# Sheet2.net
KiCad netlist of a schematic drawn in Altium Designer
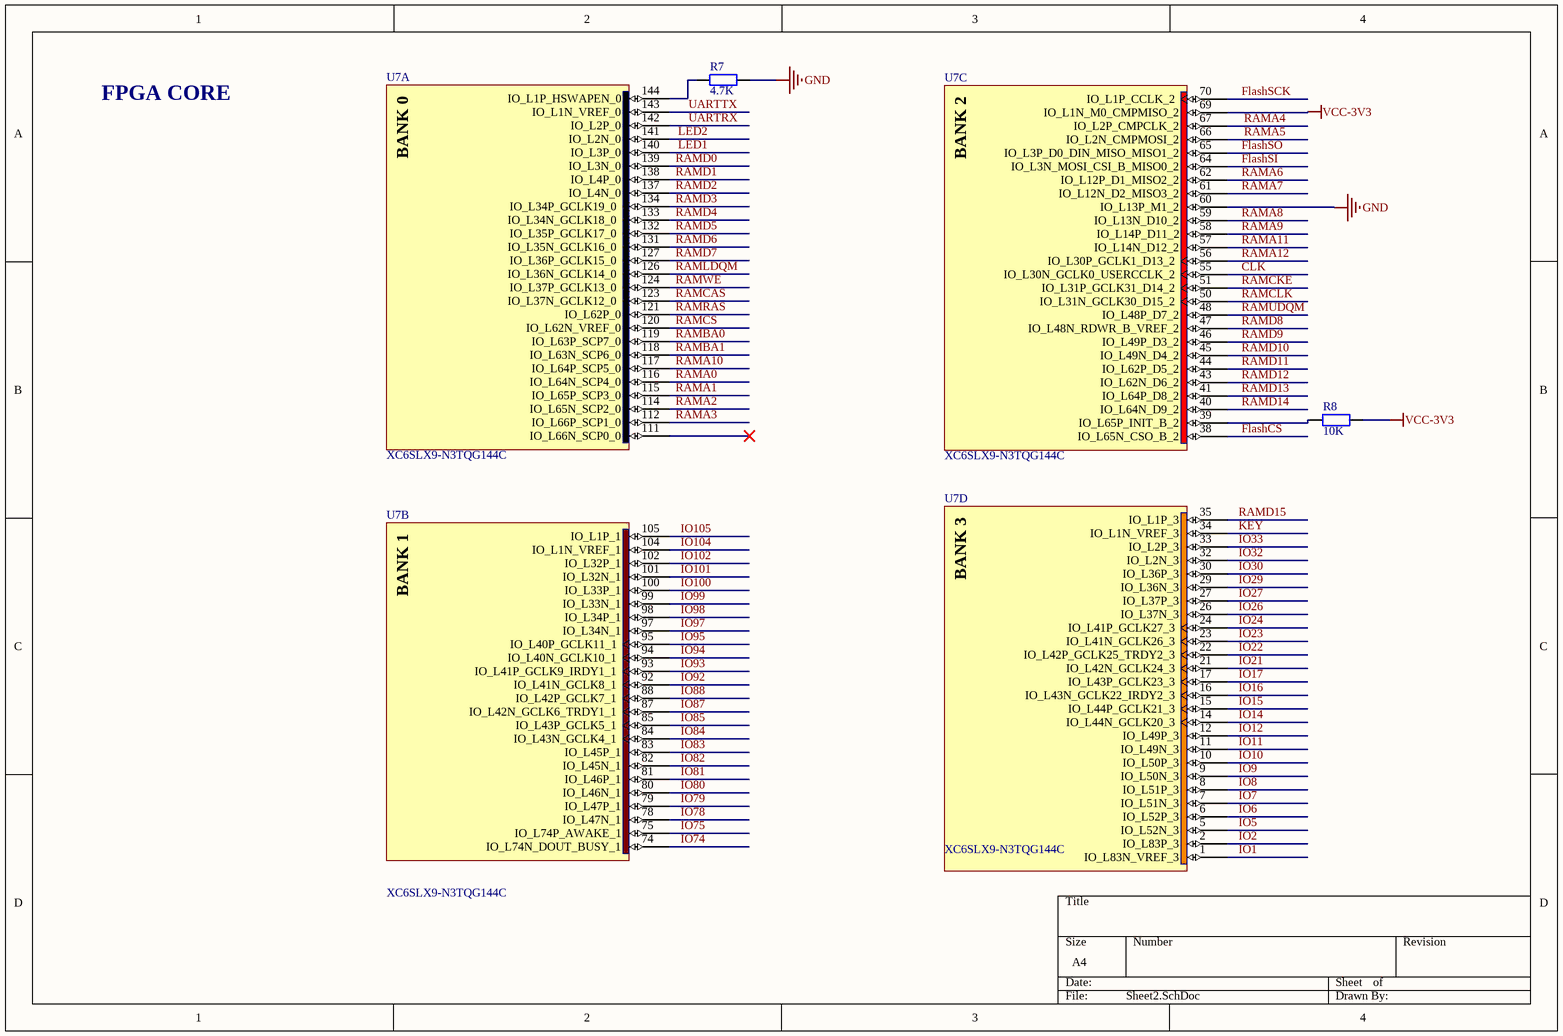
[diagram p0: Sheet2.SchDoc]

(export (version "E")
  (design (tool "Eeschema 10.0.6"))
  (components
    (comp (ref "R7")
      (value "4.7K")
      (footprint "0603_R")
      (description "贴片电阻")
      (libsource (lib "RES") (part "0603 9.1KΩ (9101) 1%"))
    )
    (comp (ref "R8")
      (value "10K")
      (footprint "0603_R")
      (description "贴片电阻")
      (libsource (lib "") (part "0603 9.1KΩ (9101) 1%_1"))
    )
    (comp (ref "U7")
      (value "XC6SLX9-N3TQG144C")
      (footprint "TQG144_N")
      (fields (field (name "PUBLISHER") "Altium Limited"))
      (libsource (lib "Xilinx Spartan-6") (part "XC6SLX9-N3TQG144C"))
    )
  )
  (nets
    (net (code "1") (name "/CLK") (class "Default")
      (node (ref "U7") (pin "55") (pinfunction "IO_L30N_GCLK0_USERCCLK_2_55") (pintype "bidirectional"))
    )
    (net (code "2") (name "/FlashCS") (class "Default")
      (node (ref "U7") (pin "38") (pinfunction "IO_L65N_CSO_B_2_38") (pintype "bidirectional"))
    )
    (net (code "3") (name "/FlashSCK") (class "Default")
      (node (ref "U7") (pin "70") (pinfunction "IO_L1P_CCLK_2_70") (pintype "bidirectional"))
    )
    (net (code "4") (name "/FlashSI") (class "Default")
      (node (ref "U7") (pin "64") (pinfunction "IO_L3N_MOSI_CSI_B_MISO0_2_64") (pintype "bidirectional"))
    )
    (net (code "5") (name "/FlashSO") (class "Default")
      (node (ref "U7") (pin "65") (pinfunction "IO_L3P_D0_DIN_MISO_MISO1_2_65") (pintype "bidirectional"))
    )
    (net (code "6") (name "/IO1") (class "Default")
      (node (ref "U7") (pin "1") (pinfunction "IO_L83N_VREF_3_1") (pintype "bidirectional"))
    )
    (net (code "7") (name "/IO2") (class "Default")
      (node (ref "U7") (pin "2") (pinfunction "IO_L83P_3_2") (pintype "bidirectional"))
    )
    (net (code "8") (name "/IO5") (class "Default")
      (node (ref "U7") (pin "5") (pinfunction "IO_L52N_3_5") (pintype "bidirectional"))
    )
    (net (code "9") (name "/IO6") (class "Default")
      (node (ref "U7") (pin "6") (pinfunction "IO_L52P_3_6") (pintype "bidirectional"))
    )
    (net (code "10") (name "/IO7") (class "Default")
      (node (ref "U7") (pin "7") (pinfunction "IO_L51N_3_7") (pintype "bidirectional"))
    )
    (net (code "11") (name "/IO8") (class "Default")
      (node (ref "U7") (pin "8") (pinfunction "IO_L51P_3_8") (pintype "bidirectional"))
    )
    (net (code "12") (name "/IO9") (class "Default")
      (node (ref "U7") (pin "9") (pinfunction "IO_L50N_3_9") (pintype "bidirectional"))
    )
    (net (code "13") (name "/IO10") (class "Default")
      (node (ref "U7") (pin "10") (pinfunction "IO_L50P_3_10") (pintype "bidirectional"))
    )
    (net (code "14") (name "/IO11") (class "Default")
      (node (ref "U7") (pin "11") (pinfunction "IO_L49N_3_11") (pintype "bidirectional"))
    )
    (net (code "15") (name "/IO12") (class "Default")
      (node (ref "U7") (pin "12") (pinfunction "IO_L49P_3_12") (pintype "bidirectional"))
    )
    (net (code "16") (name "/IO14") (class "Default")
      (node (ref "U7") (pin "14") (pinfunction "IO_L44N_GCLK20_3_14") (pintype "bidirectional"))
    )
    (net (code "17") (name "/IO15") (class "Default")
      (node (ref "U7") (pin "15") (pinfunction "IO_L44P_GCLK21_3_15") (pintype "bidirectional"))
    )
    (net (code "18") (name "/IO16") (class "Default")
      (node (ref "U7") (pin "16") (pinfunction "IO_L43N_GCLK22_IRDY2_3_16") (pintype "bidirectional"))
    )
    (net (code "19") (name "/IO17") (class "Default")
      (node (ref "U7") (pin "17") (pinfunction "IO_L43P_GCLK23_3_17") (pintype "bidirectional"))
    )
    (net (code "20") (name "/IO21") (class "Default")
      (node (ref "U7") (pin "21") (pinfunction "IO_L42N_GCLK24_3_21") (pintype "bidirectional"))
    )
    (net (code "21") (name "/IO22") (class "Default")
      (node (ref "U7") (pin "22") (pinfunction "IO_L42P_GCLK25_TRDY2_3_22") (pintype "bidirectional"))
    )
    (net (code "22") (name "/IO23") (class "Default")
      (node (ref "U7") (pin "23") (pinfunction "IO_L41N_GCLK26_3_23") (pintype "bidirectional"))
    )
    (net (code "23") (name "/IO24") (class "Default")
      (node (ref "U7") (pin "24") (pinfunction "IO_L41P_GCLK27_3_24") (pintype "bidirectional"))
    )
    (net (code "24") (name "/IO26") (class "Default")
      (node (ref "U7") (pin "26") (pinfunction "IO_L37N_3_26") (pintype "bidirectional"))
    )
    (net (code "25") (name "/IO27") (class "Default")
      (node (ref "U7") (pin "27") (pinfunction "IO_L37P_3_27") (pintype "bidirectional"))
    )
    (net (code "26") (name "/IO29") (class "Default")
      (node (ref "U7") (pin "29") (pinfunction "IO_L36N_3_29") (pintype "bidirectional"))
    )
    (net (code "27") (name "/IO30") (class "Default")
      (node (ref "U7") (pin "30") (pinfunction "IO_L36P_3_30") (pintype "bidirectional"))
    )
    (net (code "28") (name "/IO32") (class "Default")
      (node (ref "U7") (pin "32") (pinfunction "IO_L2N_3_32") (pintype "bidirectional"))
    )
    (net (code "29") (name "/IO33") (class "Default")
      (node (ref "U7") (pin "33") (pinfunction "IO_L2P_3_33") (pintype "bidirectional"))
    )
    (net (code "30") (name "/IO74") (class "Default")
      (node (ref "U7") (pin "74") (pinfunction "IO_L74N_DOUT_BUSY_1_74") (pintype "bidirectional"))
    )
    (net (code "31") (name "/IO75") (class "Default")
      (node (ref "U7") (pin "75") (pinfunction "IO_L74P_AWAKE_1_75") (pintype "bidirectional"))
    )
    (net (code "32") (name "/IO78") (class "Default")
      (node (ref "U7") (pin "78") (pinfunction "IO_L47N_1_78") (pintype "bidirectional"))
    )
    (net (code "33") (name "/IO79") (class "Default")
      (node (ref "U7") (pin "79") (pinfunction "IO_L47P_1_79") (pintype "bidirectional"))
    )
    (net (code "34") (name "/IO80") (class "Default")
      (node (ref "U7") (pin "80") (pinfunction "IO_L46N_1_80") (pintype "bidirectional"))
    )
    (net (code "35") (name "/IO81") (class "Default")
      (node (ref "U7") (pin "81") (pinfunction "IO_L46P_1_81") (pintype "bidirectional"))
    )
    (net (code "36") (name "/IO82") (class "Default")
      (node (ref "U7") (pin "82") (pinfunction "IO_L45N_1_82") (pintype "bidirectional"))
    )
    (net (code "37") (name "/IO83") (class "Default")
      (node (ref "U7") (pin "83") (pinfunction "IO_L45P_1_83") (pintype "bidirectional"))
    )
    (net (code "38") (name "/IO84") (class "Default")
      (node (ref "U7") (pin "84") (pinfunction "IO_L43N_GCLK4_1_84") (pintype "bidirectional"))
    )
    (net (code "39") (name "/IO85") (class "Default")
      (node (ref "U7") (pin "85") (pinfunction "IO_L43P_GCLK5_1_85") (pintype "bidirectional"))
    )
    (net (code "40") (name "/IO87") (class "Default")
      (node (ref "U7") (pin "87") (pinfunction "IO_L42N_GCLK6_TRDY1_1_87") (pintype "bidirectional"))
    )
    (net (code "41") (name "/IO88") (class "Default")
      (node (ref "U7") (pin "88") (pinfunction "IO_L42P_GCLK7_1_88") (pintype "bidirectional"))
    )
    (net (code "42") (name "/IO92") (class "Default")
      (node (ref "U7") (pin "92") (pinfunction "IO_L41N_GCLK8_1_92") (pintype "bidirectional"))
    )
    (net (code "43") (name "/IO93") (class "Default")
      (node (ref "U7") (pin "93") (pinfunction "IO_L41P_GCLK9_IRDY1_1_93") (pintype "bidirectional"))
    )
    (net (code "44") (name "/IO94") (class "Default")
      (node (ref "U7") (pin "94") (pinfunction "IO_L40N_GCLK10_1_94") (pintype "bidirectional"))
    )
    (net (code "45") (name "/IO95") (class "Default")
      (node (ref "U7") (pin "95") (pinfunction "IO_L40P_GCLK11_1_95") (pintype "bidirectional"))
    )
    (net (code "46") (name "/IO97") (class "Default")
      (node (ref "U7") (pin "97") (pinfunction "IO_L34N_1_97") (pintype "bidirectional"))
    )
    (net (code "47") (name "/IO98") (class "Default")
      (node (ref "U7") (pin "98") (pinfunction "IO_L34P_1_98") (pintype "bidirectional"))
    )
    (net (code "48") (name "/IO99") (class "Default")
      (node (ref "U7") (pin "99") (pinfunction "IO_L33N_1_99") (pintype "bidirectional"))
    )
    (net (code "49") (name "/IO100") (class "Default")
      (node (ref "U7") (pin "100") (pinfunction "IO_L33P_1_100") (pintype "bidirectional"))
    )
    (net (code "50") (name "/IO101") (class "Default")
      (node (ref "U7") (pin "101") (pinfunction "IO_L32N_1_101") (pintype "bidirectional"))
    )
    (net (code "51") (name "/IO102") (class "Default")
      (node (ref "U7") (pin "102") (pinfunction "IO_L32P_1_102") (pintype "bidirectional"))
    )
    (net (code "52") (name "/IO104") (class "Default")
      (node (ref "U7") (pin "104") (pinfunction "IO_L1N_VREF_1_104") (pintype "bidirectional"))
    )
    (net (code "53") (name "/IO105") (class "Default")
      (node (ref "U7") (pin "105") (pinfunction "IO_L1P_1_105") (pintype "bidirectional"))
    )
    (net (code "54") (name "/KEY") (class "Default")
      (node (ref "U7") (pin "34") (pinfunction "IO_L1N_VREF_3_34") (pintype "bidirectional"))
    )
    (net (code "55") (name "/LED1") (class "Default")
      (node (ref "U7") (pin "140") (pinfunction "IO_L3P_0_140") (pintype "bidirectional"))
    )
    (net (code "56") (name "/LED2") (class "Default")
      (node (ref "U7") (pin "141") (pinfunction "IO_L2N_0_141") (pintype "bidirectional"))
    )
    (net (code "57") (name "/RAMA0") (class "Default")
      (node (ref "U7") (pin "116") (pinfunction "IO_L64N_SCP4_0_116") (pintype "bidirectional"))
    )
    (net (code "58") (name "/RAMA1") (class "Default")
      (node (ref "U7") (pin "115") (pinfunction "IO_L65P_SCP3_0_115") (pintype "bidirectional"))
    )
    (net (code "59") (name "/RAMA2") (class "Default")
      (node (ref "U7") (pin "114") (pinfunction "IO_L65N_SCP2_0_114") (pintype "bidirectional"))
    )
    (net (code "60") (name "/RAMA3") (class "Default")
      (node (ref "U7") (pin "112") (pinfunction "IO_L66P_SCP1_0_112") (pintype "bidirectional"))
    )
    (net (code "61") (name "/RAMA4") (class "Default")
      (node (ref "U7") (pin "67") (pinfunction "IO_L2P_CMPCLK_2_67") (pintype "bidirectional"))
    )
    (net (code "62") (name "/RAMA5") (class "Default")
      (node (ref "U7") (pin "66") (pinfunction "IO_L2N_CMPMOSI_2_66") (pintype "bidirectional"))
    )
    (net (code "63") (name "/RAMA6") (class "Default")
      (node (ref "U7") (pin "62") (pinfunction "IO_L12P_D1_MISO2_2_62") (pintype "bidirectional"))
    )
    (net (code "64") (name "/RAMA7") (class "Default")
      (node (ref "U7") (pin "61") (pinfunction "IO_L12N_D2_MISO3_2_61") (pintype "bidirectional"))
    )
    (net (code "65") (name "/RAMA8") (class "Default")
      (node (ref "U7") (pin "59") (pinfunction "IO_L13N_D10_2_59") (pintype "bidirectional"))
    )
    (net (code "66") (name "/RAMA9") (class "Default")
      (node (ref "U7") (pin "58") (pinfunction "IO_L14P_D11_2_58") (pintype "bidirectional"))
    )
    (net (code "67") (name "/RAMA10") (class "Default")
      (node (ref "U7") (pin "117") (pinfunction "IO_L64P_SCP5_0_117") (pintype "bidirectional"))
    )
    (net (code "68") (name "/RAMA11") (class "Default")
      (node (ref "U7") (pin "57") (pinfunction "IO_L14N_D12_2_57") (pintype "bidirectional"))
    )
    (net (code "69") (name "/RAMA12") (class "Default")
      (node (ref "U7") (pin "56") (pinfunction "IO_L30P_GCLK1_D13_2_56") (pintype "bidirectional"))
    )
    (net (code "70") (name "/RAMBA0") (class "Default")
      (node (ref "U7") (pin "119") (pinfunction "IO_L63P_SCP7_0_119") (pintype "bidirectional"))
    )
    (net (code "71") (name "/RAMBA1") (class "Default")
      (node (ref "U7") (pin "118") (pinfunction "IO_L63N_SCP6_0_118") (pintype "bidirectional"))
    )
    (net (code "72") (name "/RAMCAS") (class "Default")
      (node (ref "U7") (pin "123") (pinfunction "IO_L37N_GCLK12_0_123") (pintype "bidirectional"))
    )
    (net (code "73") (name "/RAMCKE") (class "Default")
      (node (ref "U7") (pin "51") (pinfunction "IO_L31P_GCLK31_D14_2_51") (pintype "bidirectional"))
    )
    (net (code "74") (name "/RAMCLK") (class "Default")
      (node (ref "U7") (pin "50") (pinfunction "IO_L31N_GCLK30_D15_2_50") (pintype "bidirectional"))
    )
    (net (code "75") (name "/RAMCS") (class "Default")
      (node (ref "U7") (pin "120") (pinfunction "IO_L62N_VREF_0_120") (pintype "bidirectional"))
    )
    (net (code "76") (name "/RAMD0") (class "Default")
      (node (ref "U7") (pin "139") (pinfunction "IO_L3N_0_139") (pintype "bidirectional"))
    )
    (net (code "77") (name "/RAMD1") (class "Default")
      (node (ref "U7") (pin "138") (pinfunction "IO_L4P_0_138") (pintype "bidirectional"))
    )
    (net (code "78") (name "/RAMD2") (class "Default")
      (node (ref "U7") (pin "137") (pinfunction "IO_L4N_0_137") (pintype "bidirectional"))
    )
    (net (code "79") (name "/RAMD3") (class "Default")
      (node (ref "U7") (pin "134") (pinfunction "IO_L34P_GCLK19_0_134") (pintype "bidirectional"))
    )
    (net (code "80") (name "/RAMD4") (class "Default")
      (node (ref "U7") (pin "133") (pinfunction "IO_L34N_GCLK18_0_133") (pintype "bidirectional"))
    )
    (net (code "81") (name "/RAMD5") (class "Default")
      (node (ref "U7") (pin "132") (pinfunction "IO_L35P_GCLK17_0_132") (pintype "bidirectional"))
    )
    (net (code "82") (name "/RAMD6") (class "Default")
      (node (ref "U7") (pin "131") (pinfunction "IO_L35N_GCLK16_0_131") (pintype "bidirectional"))
    )
    (net (code "83") (name "/RAMD7") (class "Default")
      (node (ref "U7") (pin "127") (pinfunction "IO_L36P_GCLK15_0_127") (pintype "bidirectional"))
    )
    (net (code "84") (name "/RAMD8") (class "Default")
      (node (ref "U7") (pin "47") (pinfunction "IO_L48N_RDWR_B_VREF_2_47") (pintype "bidirectional"))
    )
    (net (code "85") (name "/RAMD9") (class "Default")
      (node (ref "U7") (pin "46") (pinfunction "IO_L49P_D3_2_46") (pintype "bidirectional"))
    )
    (net (code "86") (name "/RAMD10") (class "Default")
      (node (ref "U7") (pin "45") (pinfunction "IO_L49N_D4_2_45") (pintype "bidirectional"))
    )
    (net (code "87") (name "/RAMD11") (class "Default")
      (node (ref "U7") (pin "44") (pinfunction "IO_L62P_D5_2_44") (pintype "bidirectional"))
    )
    (net (code "88") (name "/RAMD12") (class "Default")
      (node (ref "U7") (pin "43") (pinfunction "IO_L62N_D6_2_43") (pintype "bidirectional"))
    )
    (net (code "89") (name "/RAMD13") (class "Default")
      (node (ref "U7") (pin "41") (pinfunction "IO_L64P_D8_2_41") (pintype "bidirectional"))
    )
    (net (code "90") (name "/RAMD14") (class "Default")
      (node (ref "U7") (pin "40") (pinfunction "IO_L64N_D9_2_40") (pintype "bidirectional"))
    )
    (net (code "91") (name "/RAMD15") (class "Default")
      (node (ref "U7") (pin "35") (pinfunction "IO_L1P_3_35") (pintype "bidirectional"))
    )
    (net (code "92") (name "/RAMLDQM") (class "Default")
      (node (ref "U7") (pin "126") (pinfunction "IO_L36N_GCLK14_0_126") (pintype "bidirectional"))
    )
    (net (code "93") (name "/RAMRAS") (class "Default")
      (node (ref "U7") (pin "121") (pinfunction "IO_L62P_0_121") (pintype "bidirectional"))
    )
    (net (code "94") (name "/RAMUDQM") (class "Default")
      (node (ref "U7") (pin "48") (pinfunction "IO_L48P_D7_2_48") (pintype "bidirectional"))
    )
    (net (code "95") (name "/RAMWE") (class "Default")
      (node (ref "U7") (pin "124") (pinfunction "IO_L37P_GCLK13_0_124") (pintype "bidirectional"))
    )
    (net (code "96") (name "/UARTRX") (class "Default")
      (node (ref "U7") (pin "142") (pinfunction "IO_L2P_0_142") (pintype "bidirectional"))
    )
    (net (code "97") (name "/UARTTX") (class "Default")
      (node (ref "U7") (pin "143") (pinfunction "IO_L1N_VREF_0_143") (pintype "bidirectional"))
    )
    (net (code "98") (name "GND") (class "Default")
      (node (ref "R7") (pin "2") (pinfunction "2_2") (pintype "passive"))
      (node (ref "U7") (pin "60") (pinfunction "IO_L13P_M1_2_60") (pintype "bidirectional"))
    )
    (net (code "99") (name "Net-(U7A-IO_L1P_HSWAPEN_0)") (class "Default")
      (node (ref "R7") (pin "1") (pinfunction "1_1") (pintype "passive"))
      (node (ref "U7") (pin "144") (pinfunction "IO_L1P_HSWAPEN_0_144") (pintype "bidirectional"))
    )
    (net (code "100") (name "Net-(U7C-IO_L65P_INIT_B_2)") (class "Default")
      (node (ref "R8") (pin "2") (pinfunction "2_2") (pintype "passive"))
      (node (ref "U7") (pin "39") (pinfunction "IO_L65P_INIT_B_2_39") (pintype "bidirectional"))
    )
    (net (code "101") (name "VCC-3V3") (class "Default")
      (node (ref "R8") (pin "1") (pinfunction "1_1") (pintype "passive"))
      (node (ref "U7") (pin "69") (pinfunction "IO_L1N_M0_CMPMISO_2_69") (pintype "bidirectional"))
    )
    (net (code "102") (name "unconnected-(U7A-IO_L66N_SCP0_0-Pad111)") (class "Default")
      (node (ref "U7") (pin "111") (pinfunction "IO_L66N_SCP0_0_111") (pintype "bidirectional+no_connect"))
    )
  )
)
